# DevBoard.net
KiCad netlist of a schematic drawn in Altium Designer
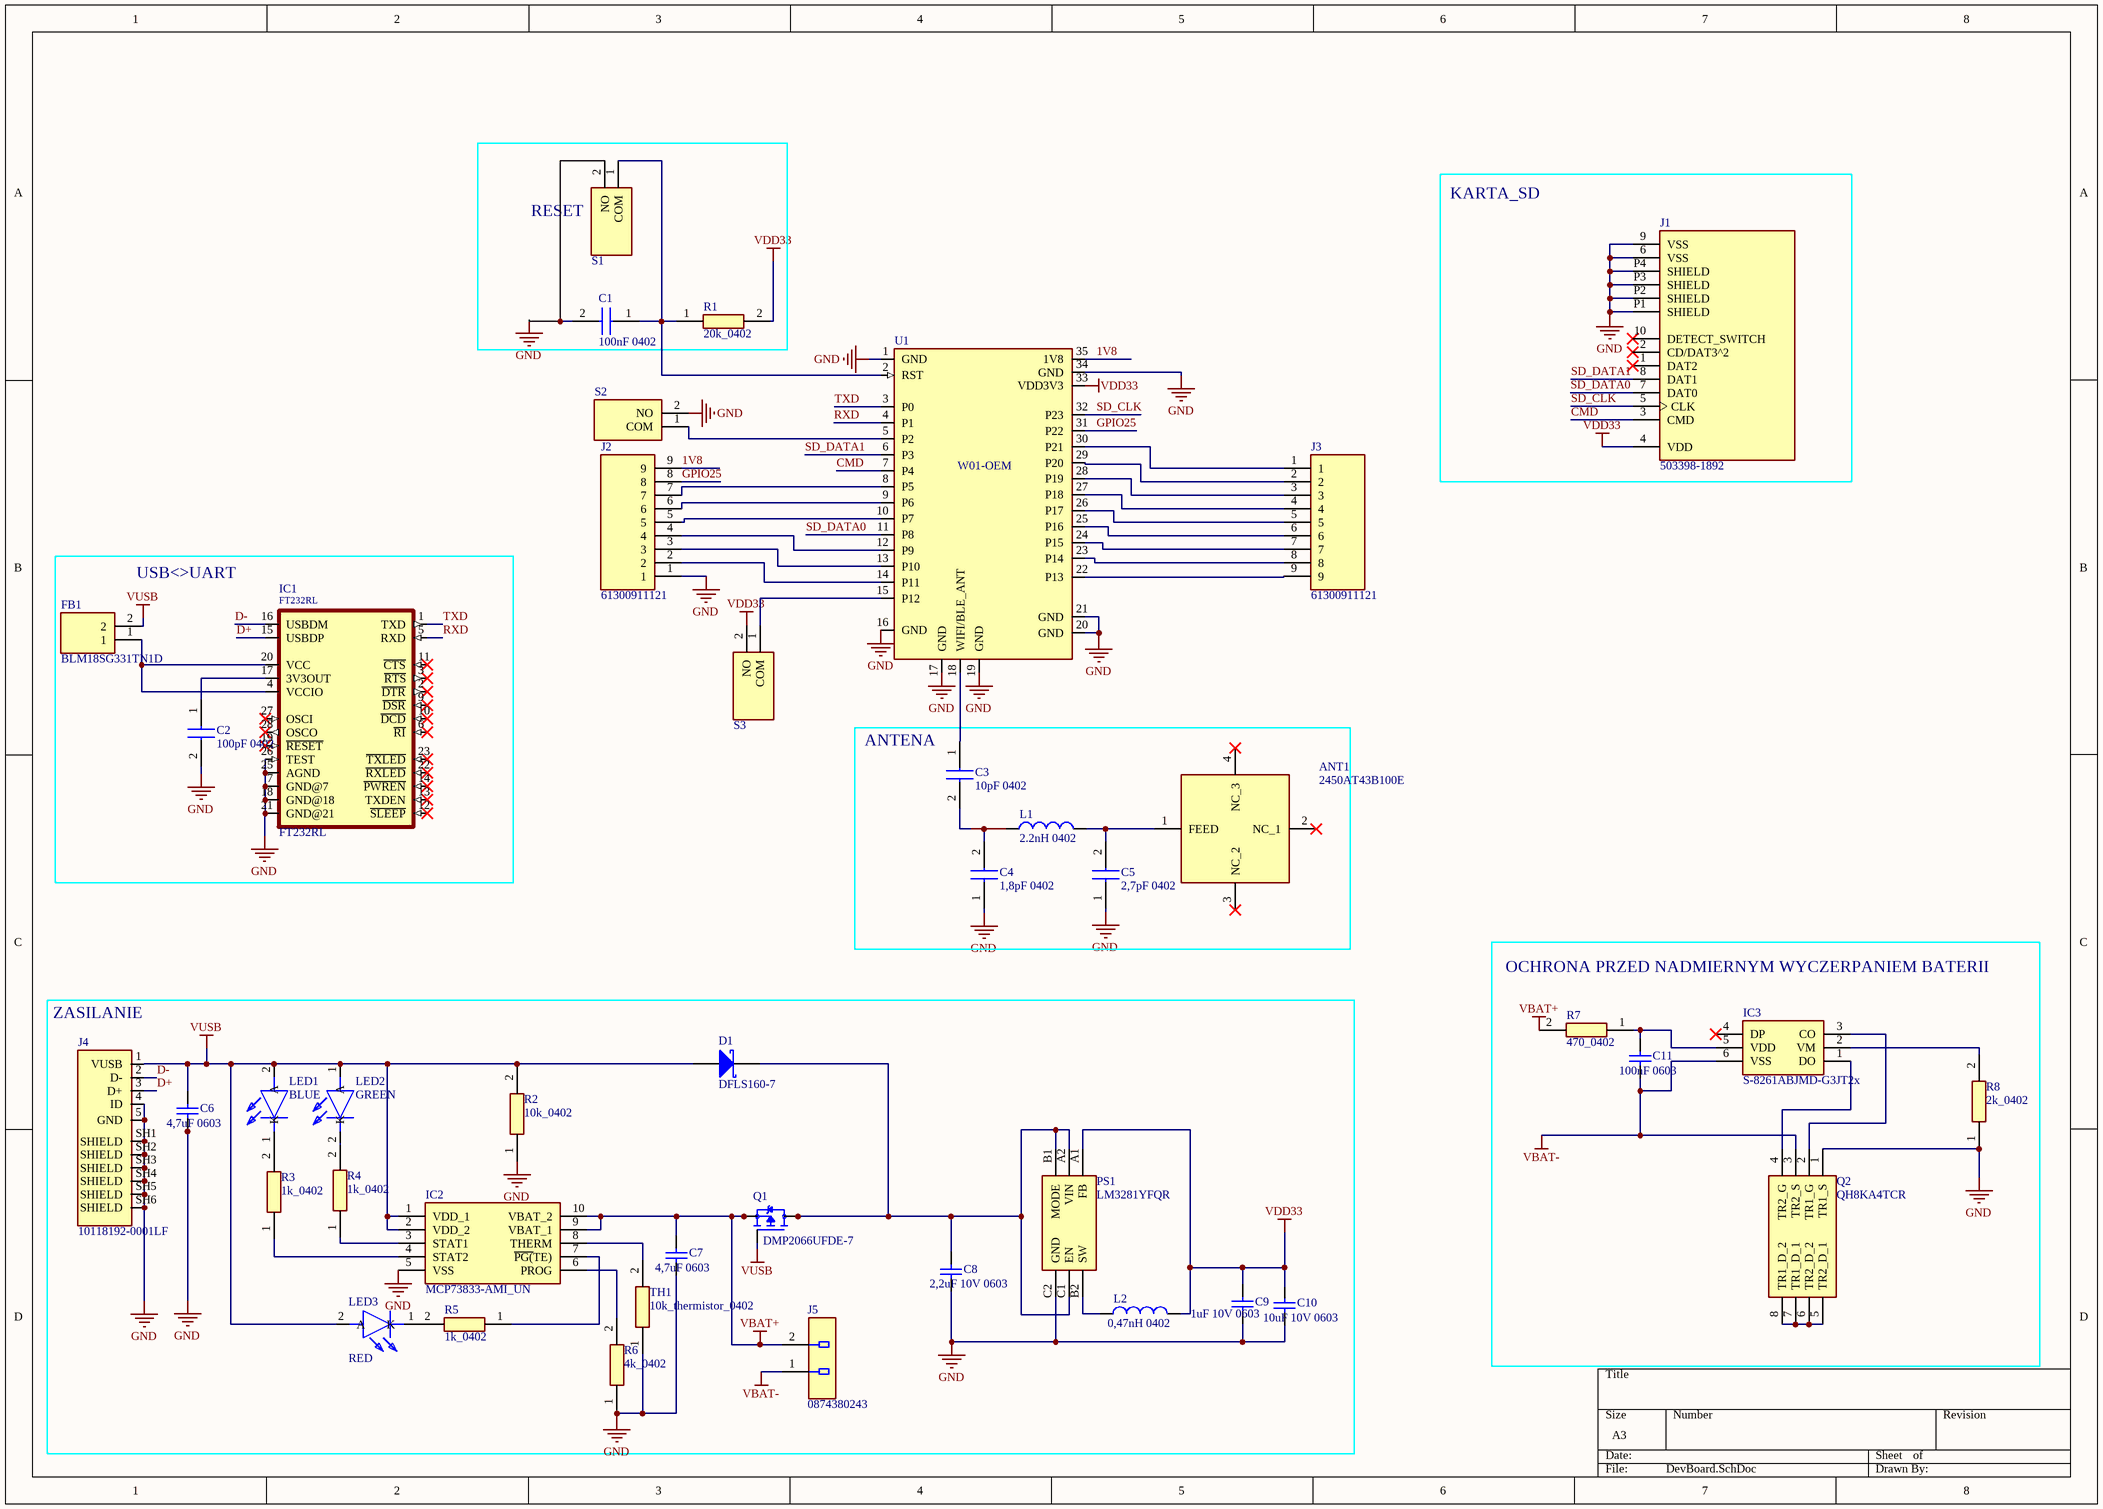
[diagram p0: DevBoard.SchDoc]

(export (version "E")
  (design (tool "Eeschema 10.0.6"))
  (components
    (comp (ref "ANT1")
      (value "2450AT43B100E")
      (footprint "SamacSys:2450AT43B100E")
      (description "Antenna")
      (fields (field (name "MOUSER PART NUMBER") "609-2450AT43B100E"))
      (libsource (lib "*") (part "2450AT43B100E"))
    )
    (comp (ref "C1")
      (value "100nF 0402")
      (footprint "SamacSys:CAPC1005X56N")
      (description "Capacitor")
      (fields
        (field (name "MANUFACTURER_PART_NUMBER") "04025A1R8BAT2A")
        (field (name "MOUSER PART NUMBER") "581-04025A1R8BAT2A")
      )
      (libsource (lib "*") (part "04025A1R8BAT2A"))
    )
    (comp (ref "C2")
      (value "100pF 0402")
      (footprint "SamacSys:CAPC1005X56N")
      (description "Capacitor")
      (fields
        (field (name "MANUFACTURER_PART_NUMBER") "04025A1R8BAT2A")
        (field (name "MOUSER PART NUMBER") "581-04025A1R8BAT2A")
      )
      (libsource (lib "*") (part "04025A1R8BAT2A"))
    )
    (comp (ref "C3")
      (value "10pF 0402")
      (footprint "SamacSys:CAPC1005X56N")
      (description "Capacitor")
      (fields
        (field (name "MANUFACTURER_PART_NUMBER") "04025A1R8BAT2A")
        (field (name "MOUSER PART NUMBER") "581-04025A1R8BAT2A")
      )
      (libsource (lib "*") (part "04025A1R8BAT2A"))
    )
    (comp (ref "C4")
      (value "1,8pF 0402")
      (footprint "SamacSys:CAPC1005X56N")
      (description "Capacitor")
      (fields
        (field (name "MANUFACTURER_PART_NUMBER") "04025A1R8BAT2A")
        (field (name "MOUSER PART NUMBER") "581-04025A1R8BAT2A")
      )
      (libsource (lib "*") (part "04025A1R8BAT2A"))
    )
    (comp (ref "C5")
      (value "2,7pF 0402")
      (footprint "SamacSys:CAPC1005X56N")
      (description "Capacitor")
      (fields
        (field (name "MANUFACTURER_PART_NUMBER") "04025A1R8BAT2A")
        (field (name "MOUSER PART NUMBER") "581-04025A1R8BAT2A")
      )
      (libsource (lib "*") (part "04025A1R8BAT2A"))
    )
    (comp (ref "C6")
      (value "4,7uF 0603")
      (footprint "CAPC0603(1608)100_L")
      (description "CAP 1uF 10V ±20% 0603 (1608 Metric) Thickness 1mm SMD")
      (fields (field (name "TOLERANCE") "Â±20%"))
      (libsource (lib "Altium Content Vault") (part "CMP-1035-02734-1"))
    )
    (comp (ref "C7")
      (value "4,7uF 0603")
      (footprint "CAPC0603(1608)100_L")
      (description "CAP 1uF 10V ±20% 0603 (1608 Metric) Thickness 1mm SMD")
      (fields (field (name "TOLERANCE") "Â±20%"))
      (libsource (lib "Altium Content Vault") (part "CMP-1035-02734-1"))
    )
    (comp (ref "C8")
      (value "2,2uF 10V 0603")
      (footprint "CAPC0603(1608)100_L")
      (description "CAP 1uF 10V ±20% 0603 (1608 Metric) Thickness 1mm SMD")
      (fields (field (name "TOLERANCE") "Â±20%"))
      (libsource (lib "Altium Content Vault") (part "CMP-1035-02734-1"))
    )
    (comp (ref "C9")
      (value "1uF 10V 0603")
      (footprint "CAPC0603(1608)100_L")
      (description "CAP 1uF 10V ±20% 0603 (1608 Metric) Thickness 1mm SMD")
      (fields (field (name "TOLERANCE") "Â±20%"))
      (libsource (lib "Altium Content Vault") (part "CAP"))
    )
    (comp (ref "C10")
      (value "10uF 10V 0603")
      (footprint "CAPC0603(1608)100_L")
      (description "CAP 1uF 10V ±20% 0603 (1608 Metric) Thickness 1mm SMD")
      (fields (field (name "TOLERANCE") "Â±20%"))
      (libsource (lib "Altium Content Vault") (part "CMP-1035-02734-1"))
    )
    (comp (ref "C11")
      (value "100nF 0603")
      (footprint "CAPC0603(1608)100_L")
      (description "CAP 1uF 10V ±20% 0603 (1608 Metric) Thickness 1mm SMD")
      (fields (field (name "TOLERANCE") "Â±20%"))
      (libsource (lib "Altium Content Vault") (part "CMP-1035-02734-1"))
    )
    (comp (ref "D1")
      (value "DFLS160-7")
      (footprint "DIOD-POWERDI123-2_V")
      (description "Schottky Barrier Rectifier, 60 V, 1 A, -65 to 150 degC, 2-Pin SMD, RoHS, Tape and Reel")
      (fields (field (name "MANUFACTURER") "Diodes Inc"))
      (libsource (lib "Altium Content Vault") (part "CMP-2000-07449-1"))
    )
    (comp (ref "FB1")
      (value "BLM18SG331TN1D")
      (footprint "SamacSys:BLM18SG121TN1J")
      (description "Ferrite Bead")
      (fields (field (name "MOUSER PART NUMBER") "81-BLM18SG331TN1D"))
      (libsource (lib "*") (part "BLM18SG331TN1D"))
    )
    (comp (ref "IC1")
      (value "FT232RL")
      (footprint "SSOP28-LD")
      (description "USB ë¸Œë¦¬ì§€, USB-UART USB 2.0 UART ì¸í„°íŽ˜ì´ìŠ¤ 28-SSOP")
      (fields (field (name "MF") "FTDI, Future"))
      (libsource (lib "FT232RL") (part "FT232RL"))
    )
    (comp (ref "IC2")
      (value "MCP73833-AMI_UN")
      (footprint "SamacSys:SOP50P490X110-10N")
      (description "Integrated Circuit")
      (fields
        (field (name "MANUFACTURER_PART_NUMBER") "MCP73833-AMI/UN")
        (field (name "MOUSER PART NUMBER") "579-MCP73833-AMI/UN")
      )
      (libsource (lib "*") (part "MCP73833-AMI_UN"))
    )
    (comp (ref "IC3")
      (value "S-8261ABJMD-G3JT2x")
      (footprint "SamacSys:SOT95P275X135-6N")
      (description "Integrated Circuit")
      (fields (field (name "MOUSER PART NUMBER") "628-S8261ACMMDG4MT2G"))
      (libsource (lib "*") (part "S-8261ACMMD-G4MT2U"))
    )
    (comp (ref "J1")
      (value "503398-1892")
      (footprint "MOLEX_503398-1892")
      (description "9 _8 + 1_ Position Card Connector microSDâ„¢ Surface Mount, Right Angle Gold")
      (fields (field (name "MP") "5033981892") (field (name "DIGI-KEY_PART_NUMBER") "WM11190CT-ND"))
      (libsource (lib "503398-1892") (part "503398-1892"))
    )
    (comp (ref "J2")
      (value "61300911121")
      (footprint "SamacSys:HDRV9W95P0X254_1X9_2286X254X874P")
      (description "Connector")
      (fields (field (name "MOUSER PART NUMBER") "710-61300911121"))
      (libsource (lib "") (part "61300911121_1"))
    )
    (comp (ref "J3")
      (value "61300911121")
      (footprint "SamacSys:HDRV9W95P0X254_1X9_2286X254X874P")
      (description "Connector")
      (fields (field (name "MOUSER PART NUMBER") "710-61300911121"))
      (libsource (lib "*") (part "61300911121"))
    )
    (comp (ref "J4")
      (value "10118192-0001LF")
      (footprint "SamacSys:101181920001LF")
      (description "USB - micro B USB 2.0 Receptacle Connector 5 Position Surface Mount, Right Angle")
      (fields (field (name "MF") "Amphenol ICC"))
      (libsource (lib "10118192-0001LF") (part "10118192-0001LF"))
    )
    (comp (ref "J5")
      (value "Conn_Molex_0874380243_eec")
      (footprint "Molex_0874380243_0")
      (description "CONN HEADER 2POS 1.5MM R/A SMD")
      (fields
        (field (name "PART NUMBER") "0874380243")
        (field (name "MANUFACTURER") "Molex")
        (field (name "MOUSER PART NUMBER") "538-87438-0243")
      )
      (libsource (lib "Conn_Molex_0874380243_eec") (part "Conn_Molex_0874380243_eec"))
    )
    (comp (ref "L1")
      (value "2.2nH 0402")
      (footprint "INDC1006X60X20LL10T10")
      (description "Chip Inductor, 10 nH, +/- 5%, 500 mA, -55 to 125 degC, 0402 (1005 Metric), RoHS, Tape and Reel")
      (fields (field (name "MANUFACTURER") "Murata"))
      (libsource (lib "Altium Content Vault") (part "IND-2"))
    )
    (comp (ref "L2")
      (value "0,47nH 0402")
      (footprint "INDC1006X60X20LL10T10")
      (description "Chip Inductor, 10 nH, +/- 5%, 500 mA, -55 to 125 degC, 0402 (1005 Metric), RoHS, Tape and Reel")
      (fields (field (name "MANUFACTURER") "Murata"))
      (libsource (lib "Altium Content Vault") (part "IND-2"))
    )
    (comp (ref "LED1")
      (value "BLUE")
      (footprint "SamacSys:KBDELPS212QHRI24Z55510S")
      (description "LED_BLUE")
      (fields
        (field (name "MANUFACTURER_PART_NUMBER") "KB DELPS2.12-QHRI-24-Z555-10-S")
        (field (name "MOUSER PART NUMBER") "720-KBDELPS212A6350")
      )
      (libsource (lib "*") (part "KB_DELPS2.12-QHRI-24-Z555-10-S"))
    )
    (comp (ref "LED2")
      (value "GREEN")
      (footprint "SamacSys:KGDELLS122JGKH24")
      (description "LED_GREEN")
      (fields
        (field (name "MANUFACTURER_PART_NUMBER") "KG DELLS1.22-JGKH-24")
        (field (name "MOUSER PART NUMBER") "720-KGDELLS122A4849")
      )
      (libsource (lib "*") (part "KG_DELLS1.22-JGKH-24"))
    )
    (comp (ref "LED3")
      (value "RED")
      (footprint "SamacSys:KRDELPS122UHVI26H3Q4")
      (description "LED_RED")
      (fields
        (field (name "MANUFACTURER_PART_NUMBER") "KR DELPS1.22-UHVI-26-H3Q4")
        (field (name "MOUSER PART NUMBER") "720-KRDELPS122A5163")
      )
      (libsource (lib "*") (part "KR_DELPS1.22-UHVI-26-H3Q4"))
    )
    (comp (ref "PS1")
      (value "LM3281YFQR")
      (footprint "SamacSys:BGA6C40P2X3_116X144X68")
      (description "Power Supply")
      (fields (field (name "MOUSER PART NUMBER") "595-LM3281YFQR"))
      (libsource (lib "*") (part "LM3281YFQR"))
    )
    (comp (ref "Q1")
      (value "DMP2066UFDE-7")
      (footprint "MOSFET_DMP2066UFDE-7")
      (description "P-Channel 20V 6.2A (Ta) 660mW (Ta) Surface Mount U-DFN2020-6 (Type E)")
      (fields (field (name "MF") "Diodes Inc."))
      (libsource (lib "DMP2066UFDE-7") (part "DMP2066UFDE-7"))
    )
    (comp (ref "Q2")
      (value "QH8KA4TCR")
      (footprint "SamacSys:SOTFL65P280X85-8N")
      (description "MOSFET (N-Channel)")
      (fields (field (name "MOUSER PART NUMBER") "755-QH8KA4TCR"))
      (libsource (lib "*") (part "QH8KA4TCR"))
    )
    (comp (ref "R1")
      (value "20k_0402")
      (footprint "SamacSys:RESC1005X40N")
      (description "Resistor")
      (fields
        (field (name "MANUFACTURER_PART_NUMBER") "CR0402-FX-2002GLF")
        (field (name "MOUSER PART NUMBER") "652-CR0402FX-2002GLF")
      )
      (libsource (lib "") (part "CR0402-FX-2002GLF_2"))
    )
    (comp (ref "R2")
      (value "10k_0402")
      (footprint "SamacSys:RESC1005X40N")
      (description "Resistor")
      (fields
        (field (name "MANUFACTURER_PART_NUMBER") "CR0402-FX-2002GLF")
        (field (name "MOUSER PART NUMBER") "652-CR0402FX-2002GLF")
      )
      (libsource (lib "*") (part "CR0402-FX-2002GLF"))
    )
    (comp (ref "R3")
      (value "1k_0402")
      (footprint "SamacSys:RESC1005X40N")
      (description "Resistor")
      (fields
        (field (name "MANUFACTURER_PART_NUMBER") "CR0402-FX-2002GLF")
        (field (name "MOUSER PART NUMBER") "652-CR0402FX-2002GLF")
      )
      (libsource (lib "*") (part "CR0402-FX-2002GLF"))
    )
    (comp (ref "R4")
      (value "1k_0402")
      (footprint "SamacSys:RESC1005X40N")
      (description "Resistor")
      (fields
        (field (name "MANUFACTURER_PART_NUMBER") "CR0402-FX-2002GLF")
        (field (name "MOUSER PART NUMBER") "652-CR0402FX-2002GLF")
      )
      (libsource (lib "*") (part "CR0402-FX-2002GLF"))
    )
    (comp (ref "R5")
      (value "1k_0402")
      (footprint "SamacSys:RESC1005X40N")
      (description "Resistor")
      (fields
        (field (name "MANUFACTURER_PART_NUMBER") "CR0402-FX-2002GLF")
        (field (name "MOUSER PART NUMBER") "652-CR0402FX-2002GLF")
      )
      (libsource (lib "") (part "CR0402-FX-2002GLF_1"))
    )
    (comp (ref "R6")
      (value "4k_0402")
      (footprint "SamacSys:RESC1005X40N")
      (description "Resistor")
      (fields
        (field (name "MANUFACTURER_PART_NUMBER") "CR0402-FX-2002GLF")
        (field (name "MOUSER PART NUMBER") "652-CR0402FX-2002GLF")
      )
      (libsource (lib "*") (part "CR0402-FX-2002GLF"))
    )
    (comp (ref "R7")
      (value "470_0402")
      (footprint "SamacSys:RESC1005X40N")
      (description "Resistor")
      (fields
        (field (name "MANUFACTURER_PART_NUMBER") "CR0402-FX-2002GLF")
        (field (name "MOUSER PART NUMBER") "652-CR0402FX-2002GLF")
      )
      (libsource (lib "") (part "CR0402-FX-2002GLF_1"))
    )
    (comp (ref "R8")
      (value "2k_0402")
      (footprint "SamacSys:RESC1005X40N")
      (description "Resistor")
      (fields
        (field (name "MANUFACTURER_PART_NUMBER") "CR0402-FX-2002GLF")
        (field (name "MOUSER PART NUMBER") "652-CR0402FX-2002GLF")
      )
      (libsource (lib "*") (part "CR0402-FX-2002GLF"))
    )
    (comp (ref "S1")
      (value "PTS636_SM43J_SMTR_LFS")
      (footprint "SamacSys:PTS636SM43JSMTRLFS")
      (description "Switch")
      (fields
        (field (name "MANUFACTURER_PART_NUMBER") "PTS636 SM43J SMTR LFS")
        (field (name "MOUSER PART NUMBER") "611-PTS636SM43JSMTRL")
      )
      (libsource (lib "") (part "PTS636_SM43J_SMTR_LFS_1"))
    )
    (comp (ref "S2")
      (value "PTS636_SM43J_SMTR_LFS")
      (footprint "SamacSys:PTS636SM43JSMTRLFS")
      (description "Switch")
      (fields
        (field (name "MANUFACTURER_PART_NUMBER") "PTS636 SM43J SMTR LFS")
        (field (name "MOUSER PART NUMBER") "611-PTS636SM43JSMTRL")
      )
      (libsource (lib "*") (part "PTS636_SM43J_SMTR_LFS"))
    )
    (comp (ref "S3")
      (value "PTS636_SM43J_SMTR_LFS")
      (footprint "SamacSys:PTS636SM43JSMTRLFS")
      (description "Switch")
      (fields
        (field (name "MANUFACTURER_PART_NUMBER") "PTS636 SM43J SMTR LFS")
        (field (name "MOUSER PART NUMBER") "611-PTS636SM43JSMTRL")
      )
      (libsource (lib "") (part "PTS636_SM43J_SMTR_LFS_1"))
    )
    (comp (ref "TH1")
      (value "10k_thermistor_0402")
      (footprint "SamacSys:RESC1005X40N")
      (description "NCU15XH103D60RC")
      (fields
        (field (name "MANUFACTURER_PART_NUMBER") "CR0402-FX-2002GLF")
        (field (name "MOUSER PART NUMBER") "652-CR0402FX-2002GLF")
      )
      (libsource (lib "*") (part "CR0402-FX-2002GLF"))
    )
    (comp (ref "U1")
      (value "W01-OEM")
      (footprint "SnapEDApcb:PYCOM_W01-OEM")
      (fields (field (name "MF") "Pycom"))
      (libsource (lib "SnapEDAsch") (part "W01-OEM"))
    )
  )
  (nets
    (net (code "1") (name "/1V8") (class "Default")
      (node (ref "J2") (pin "9") (pinfunction "9_9") (pintype "passive"))
      (node (ref "U1") (pin "35") (pinfunction "1V8_35") (pintype "power_in"))
    )
    (net (code "2") (name "/CMD") (class "Default")
      (node (ref "J1") (pin "3") (pinfunction "CMD_3") (pintype "passive"))
      (node (ref "U1") (pin "7") (pinfunction "P4_7") (pintype "bidirectional"))
    )
    (net (code "3") (name "/D+") (class "Default")
      (node (ref "IC1") (pin "15") (pinfunction "USBDP_15") (pintype "bidirectional"))
      (node (ref "J4") (pin "3") (pinfunction "D+_3") (pintype "passive"))
    )
    (net (code "4") (name "/D-") (class "Default")
      (node (ref "IC1") (pin "16") (pinfunction "USBDM_16") (pintype "bidirectional"))
      (node (ref "J4") (pin "2") (pinfunction "D-_2") (pintype "passive"))
    )
    (net (code "5") (name "/GPIO25") (class "Default")
      (node (ref "J2") (pin "8") (pinfunction "8_8") (pintype "passive"))
      (node (ref "U1") (pin "31") (pinfunction "P22_31") (pintype "bidirectional"))
    )
    (net (code "6") (name "/RXD") (class "Default")
      (node (ref "IC1") (pin "5") (pinfunction "RXD_5") (pintype "input"))
      (node (ref "U1") (pin "4") (pinfunction "P1_4") (pintype "bidirectional"))
    )
    (net (code "7") (name "/SD_CLK") (class "Default")
      (node (ref "J1") (pin "5") (pinfunction "CLK_5") (pintype "passive"))
      (node (ref "U1") (pin "32") (pinfunction "P23_32") (pintype "bidirectional"))
    )
    (net (code "8") (name "/SD_DATA0") (class "Default")
      (node (ref "J1") (pin "7") (pinfunction "DAT0_7") (pintype "passive"))
      (node (ref "U1") (pin "11") (pinfunction "P8_11") (pintype "bidirectional"))
    )
    (net (code "9") (name "/SD_DATA1") (class "Default")
      (node (ref "J1") (pin "8") (pinfunction "DAT1_8") (pintype "passive"))
      (node (ref "U1") (pin "6") (pinfunction "P3_6") (pintype "bidirectional"))
    )
    (net (code "10") (name "/TXD") (class "Default")
      (node (ref "IC1") (pin "1") (pinfunction "TXD_1") (pintype "output"))
      (node (ref "U1") (pin "3") (pinfunction "P0_3") (pintype "bidirectional"))
    )
    (net (code "11") (name "GND") (class "Default")
      (node (ref "C1") (pin "2") (pinfunction "2_2") (pintype "passive"))
      (node (ref "C10") (pin "1") (pinfunction "1_1") (pintype "passive"))
      (node (ref "C2") (pin "2") (pinfunction "2_2") (pintype "passive"))
      (node (ref "C4") (pin "1") (pinfunction "1_1") (pintype "passive"))
      (node (ref "C5") (pin "1") (pinfunction "1_1") (pintype "passive"))
      (node (ref "C6") (pin "1") (pinfunction "1_1") (pintype "passive"))
      (node (ref "C7") (pin "1") (pinfunction "1_1") (pintype "passive"))
      (node (ref "C8") (pin "1") (pinfunction "1_1") (pintype "passive"))
      (node (ref "C9") (pin "1") (pinfunction "1_1") (pintype "passive"))
      (node (ref "IC1") (pin "18") (pinfunction "GND@18_18") (pintype "power_in"))
      (node (ref "IC1") (pin "21") (pinfunction "GND@21_21") (pintype "power_in"))
      (node (ref "IC1") (pin "25") (pinfunction "AGND_25") (pintype "power_in"))
      (node (ref "IC1") (pin "26") (pinfunction "TEST_26") (pintype "input"))
      (node (ref "IC1") (pin "7") (pinfunction "GND@7_7") (pintype "power_in"))
      (node (ref "IC2") (pin "5") (pinfunction "VSS_5") (pintype "passive"))
      (node (ref "J1") (pin "6") (pinfunction "VSS_6") (pintype "power_in"))
      (node (ref "J1") (pin "9") (pinfunction "VSS_9") (pintype "power_in"))
      (node (ref "J1") (pin "P1") (pinfunction "SHIELD_P1") (pintype "passive"))
      (node (ref "J1") (pin "P2") (pinfunction "SHIELD_P2") (pintype "passive"))
      (node (ref "J1") (pin "P3") (pinfunction "SHIELD_P3") (pintype "passive"))
      (node (ref "J1") (pin "P4") (pinfunction "SHIELD_P4") (pintype "passive"))
      (node (ref "J2") (pin "1") (pinfunction "1_1") (pintype "passive"))
      (node (ref "J4") (pin "4") (pinfunction "ID_4") (pintype "passive"))
      (node (ref "J4") (pin "5") (pinfunction "GND_5") (pintype "passive"))
      (node (ref "J4") (pin "SH1") (pinfunction "SHIELD_SH1") (pintype "passive"))
      (node (ref "J4") (pin "SH2") (pinfunction "SHIELD_SH2") (pintype "passive"))
      (node (ref "J4") (pin "SH3") (pinfunction "SHIELD_SH3") (pintype "passive"))
      (node (ref "J4") (pin "SH4") (pinfunction "SHIELD_SH4") (pintype "passive"))
      (node (ref "J4") (pin "SH5") (pinfunction "SHIELD_SH5") (pintype "passive"))
      (node (ref "J4") (pin "SH6") (pinfunction "SHIELD_SH6") (pintype "passive"))
      (node (ref "PS1") (pin "C2") (pinfunction "GND_C2") (pintype "passive"))
      (node (ref "Q2") (pin "1") (pinfunction "TR1_S_1") (pintype "passive"))
      (node (ref "R2") (pin "1") (pinfunction "1_1") (pintype "passive"))
      (node (ref "R6") (pin "1") (pinfunction "1_1") (pintype "passive"))
      (node (ref "R8") (pin "1") (pinfunction "1_1") (pintype "passive"))
      (node (ref "S1") (pin "2") (pinfunction "NO_2") (pintype "passive"))
      (node (ref "S2") (pin "2") (pinfunction "NO_2") (pintype "passive"))
      (node (ref "TH1") (pin "1") (pinfunction "1_1") (pintype "passive"))
      (node (ref "U1") (pin "1") (pinfunction "GND_1") (pintype "power_in"))
      (node (ref "U1") (pin "16") (pinfunction "GND_16") (pintype "power_in"))
      (node (ref "U1") (pin "17") (pinfunction "GND_17") (pintype "power_in"))
      (node (ref "U1") (pin "19") (pinfunction "GND_19") (pintype "power_in"))
      (node (ref "U1") (pin "20") (pinfunction "GND_20") (pintype "power_in"))
      (node (ref "U1") (pin "21") (pinfunction "GND_21") (pintype "power_in"))
      (node (ref "U1") (pin "34") (pinfunction "GND_34") (pintype "power_in"))
    )
    (net (code "12") (name "Net-(ANT1-FEED)") (class "Default")
      (node (ref "ANT1") (pin "1") (pinfunction "FEED_1") (pintype "passive"))
      (node (ref "C5") (pin "2") (pinfunction "2_2") (pintype "passive"))
      (node (ref "L1") (pin "2") (pinfunction "2_2") (pintype "passive"))
    )
    (net (code "13") (name "Net-(C3-Pad2)") (class "Default")
      (node (ref "C3") (pin "2") (pinfunction "2_2") (pintype "passive"))
      (node (ref "C4") (pin "2") (pinfunction "2_2") (pintype "passive"))
      (node (ref "L1") (pin "1") (pinfunction "1_1") (pintype "passive"))
    )
    (net (code "14") (name "Net-(D1-K)") (class "Default")
      (node (ref "C8") (pin "2") (pinfunction "2_2") (pintype "passive"))
      (node (ref "D1") (pin "2") (pinfunction "K_2") (pintype "passive"))
      (node (ref "PS1") (pin "A2") (pinfunction "VIN_A2") (pintype "passive"))
      (node (ref "PS1") (pin "B1") (pinfunction "MODE_B1") (pintype "passive"))
      (node (ref "PS1") (pin "C1") (pinfunction "EN_C1") (pintype "passive"))
      (node (ref "Q1") (pin "1") (pinfunction "D_1") (pintype "passive"))
      (node (ref "Q1") (pin "2") (pinfunction "D_2") (pintype "passive"))
      (node (ref "Q1") (pin "5") (pinfunction "D_5") (pintype "passive"))
      (node (ref "Q1") (pin "6") (pinfunction "D_6") (pintype "passive"))
    )
    (net (code "15") (name "Net-(IC1-3V3OUT)") (class "Default")
      (node (ref "C2") (pin "1") (pinfunction "1_1") (pintype "passive"))
      (node (ref "IC1") (pin "17") (pinfunction "3V3OUT_17") (pintype "power_in"))
    )
    (net (code "16") (name "Net-(IC1-VCC)") (class "Default")
      (node (ref "FB1") (pin "1") (pinfunction "1_1") (pintype "passive"))
      (node (ref "IC1") (pin "20") (pinfunction "VCC_20") (pintype "power_in"))
      (node (ref "IC1") (pin "4") (pinfunction "VCCIO_4") (pintype "power_in"))
    )
    (net (code "17") (name "Net-(IC2-PROG)") (class "Default")
      (node (ref "IC2") (pin "6") (pinfunction "PROG_6") (pintype "passive"))
      (node (ref "R6") (pin "2") (pinfunction "2_2") (pintype "passive"))
    )
    (net (code "18") (name "Net-(IC2-STAT1)") (class "Default")
      (node (ref "IC2") (pin "3") (pinfunction "STAT1_3") (pintype "passive"))
      (node (ref "R4") (pin "1") (pinfunction "1_1") (pintype "passive"))
    )
    (net (code "19") (name "Net-(IC2-STAT2)") (class "Default")
      (node (ref "IC2") (pin "4") (pinfunction "STAT2_4") (pintype "passive"))
      (node (ref "R3") (pin "1") (pinfunction "1_1") (pintype "passive"))
    )
    (net (code "20") (name "Net-(IC2-THERM)") (class "Default")
      (node (ref "IC2") (pin "8") (pinfunction "THERM_8") (pintype "passive"))
      (node (ref "TH1") (pin "2") (pinfunction "2_2") (pintype "passive"))
    )
    (net (code "21") (name "Net-(IC2-~{PG(}TE))") (class "Default")
      (node (ref "IC2") (pin "7") (pinfunction "~{PG(}TE)_7") (pintype "passive"))
      (node (ref "R5") (pin "1") (pinfunction "1_1") (pintype "passive"))
    )
    (net (code "22") (name "Net-(IC3-CO)") (class "Default")
      (node (ref "IC3") (pin "3") (pinfunction "CO_3") (pintype "passive"))
      (node (ref "Q2") (pin "2") (pinfunction "TR1_G_2") (pintype "passive"))
    )
    (net (code "23") (name "Net-(IC3-DO)") (class "Default")
      (node (ref "IC3") (pin "1") (pinfunction "DO_1") (pintype "passive"))
      (node (ref "Q2") (pin "4") (pinfunction "TR2_G_4") (pintype "passive"))
    )
    (net (code "24") (name "Net-(IC3-VDD)") (class "Default")
      (node (ref "C11") (pin "2") (pinfunction "2_2") (pintype "passive"))
      (node (ref "IC3") (pin "5") (pinfunction "VDD_5") (pintype "passive"))
      (node (ref "R7") (pin "1") (pinfunction "1_1") (pintype "passive"))
    )
    (net (code "25") (name "Net-(IC3-VM)") (class "Default")
      (node (ref "IC3") (pin "2") (pinfunction "VM_2") (pintype "passive"))
      (node (ref "R8") (pin "2") (pinfunction "2_2") (pintype "passive"))
    )
    (net (code "26") (name "Net-(LED1-K)") (class "Default")
      (node (ref "LED1") (pin "1") (pinfunction "K_1") (pintype "passive"))
      (node (ref "R3") (pin "2") (pinfunction "2_2") (pintype "passive"))
    )
    (net (code "27") (name "Net-(LED2-K)") (class "Default")
      (node (ref "LED2") (pin "2") (pinfunction "K_2") (pintype "passive"))
      (node (ref "R4") (pin "2") (pinfunction "2_2") (pintype "passive"))
    )
    (net (code "28") (name "Net-(LED3-K)") (class "Default")
      (node (ref "LED3") (pin "1") (pinfunction "K_1") (pintype "passive"))
      (node (ref "R5") (pin "2") (pinfunction "2_2") (pintype "passive"))
    )
    (net (code "29") (name "Net-(PS1-SW)") (class "Default")
      (node (ref "L2") (pin "1") (pinfunction "1_1") (pintype "passive"))
      (node (ref "PS1") (pin "B2") (pinfunction "SW_B2") (pintype "passive"))
    )
    (net (code "30") (name "Net-(Q2-TR1_D_1)") (class "Default")
      (node (ref "Q2") (pin "5") (pinfunction "TR2_D_1_5") (pintype "passive"))
      (node (ref "Q2") (pin "6") (pinfunction "TR2_D_2_6") (pintype "passive"))
      (node (ref "Q2") (pin "7") (pinfunction "TR1_D_1_7") (pintype "passive"))
      (node (ref "Q2") (pin "8") (pinfunction "TR1_D_2_8") (pintype "passive"))
    )
    (net (code "31") (name "Net-(S1-COM)") (class "Default")
      (node (ref "C1") (pin "1") (pinfunction "1_1") (pintype "passive"))
      (node (ref "R1") (pin "1") (pinfunction "1_1") (pintype "passive"))
      (node (ref "S1") (pin "1") (pinfunction "COM_1") (pintype "passive"))
      (node (ref "U1") (pin "2") (pinfunction "RST_2") (pintype "input"))
    )
    (net (code "32") (name "Net-(S2-COM)") (class "Default")
      (node (ref "S2") (pin "1") (pinfunction "COM_1") (pintype "passive"))
      (node (ref "U1") (pin "5") (pinfunction "P2_5") (pintype "bidirectional"))
    )
    (net (code "33") (name "Net-(S3-COM)") (class "Default")
      (node (ref "S3") (pin "1") (pinfunction "COM_1") (pintype "passive"))
      (node (ref "U1") (pin "15") (pinfunction "P12_15") (pintype "bidirectional"))
    )
    (net (code "34") (name "Net-(U1-P5)") (class "Default")
      (node (ref "J2") (pin "7") (pinfunction "7_7") (pintype "passive"))
      (node (ref "U1") (pin "8") (pinfunction "P5_8") (pintype "bidirectional"))
    )
    (net (code "35") (name "Net-(U1-P6)") (class "Default")
      (node (ref "J2") (pin "6") (pinfunction "6_6") (pintype "passive"))
      (node (ref "U1") (pin "9") (pinfunction "P6_9") (pintype "bidirectional"))
    )
    (net (code "36") (name "Net-(U1-P7)") (class "Default")
      (node (ref "J2") (pin "5") (pinfunction "5_5") (pintype "passive"))
      (node (ref "U1") (pin "10") (pinfunction "P7_10") (pintype "bidirectional"))
    )
    (net (code "37") (name "Net-(U1-P9)") (class "Default")
      (node (ref "J2") (pin "4") (pinfunction "4_4") (pintype "passive"))
      (node (ref "U1") (pin "12") (pinfunction "P9_12") (pintype "bidirectional"))
    )
    (net (code "38") (name "Net-(U1-P10)") (class "Default")
      (node (ref "J2") (pin "3") (pinfunction "3_3") (pintype "passive"))
      (node (ref "U1") (pin "13") (pinfunction "P10_13") (pintype "bidirectional"))
    )
    (net (code "39") (name "Net-(U1-P11)") (class "Default")
      (node (ref "J2") (pin "2") (pinfunction "2_2") (pintype "passive"))
      (node (ref "U1") (pin "14") (pinfunction "P11_14") (pintype "bidirectional"))
    )
    (net (code "40") (name "Net-(U1-P13)") (class "Default")
      (node (ref "J3") (pin "9") (pinfunction "9_9") (pintype "passive"))
      (node (ref "U1") (pin "22") (pinfunction "P13_22") (pintype "bidirectional"))
    )
    (net (code "41") (name "Net-(U1-P14)") (class "Default")
      (node (ref "J3") (pin "8") (pinfunction "8_8") (pintype "passive"))
      (node (ref "U1") (pin "23") (pinfunction "P14_23") (pintype "bidirectional"))
    )
    (net (code "42") (name "Net-(U1-P15)") (class "Default")
      (node (ref "J3") (pin "7") (pinfunction "7_7") (pintype "passive"))
      (node (ref "U1") (pin "24") (pinfunction "P15_24") (pintype "bidirectional"))
    )
    (net (code "43") (name "Net-(U1-P16)") (class "Default")
      (node (ref "J3") (pin "6") (pinfunction "6_6") (pintype "passive"))
      (node (ref "U1") (pin "25") (pinfunction "P16_25") (pintype "bidirectional"))
    )
    (net (code "44") (name "Net-(U1-P17)") (class "Default")
      (node (ref "J3") (pin "5") (pinfunction "5_5") (pintype "passive"))
      (node (ref "U1") (pin "26") (pinfunction "P17_26") (pintype "bidirectional"))
    )
    (net (code "45") (name "Net-(U1-P18)") (class "Default")
      (node (ref "J3") (pin "4") (pinfunction "4_4") (pintype "passive"))
      (node (ref "U1") (pin "27") (pinfunction "P18_27") (pintype "bidirectional"))
    )
    (net (code "46") (name "Net-(U1-P19)") (class "Default")
      (node (ref "J3") (pin "3") (pinfunction "3_3") (pintype "passive"))
      (node (ref "U1") (pin "28") (pinfunction "P19_28") (pintype "bidirectional"))
    )
    (net (code "47") (name "Net-(U1-P20)") (class "Default")
      (node (ref "J3") (pin "2") (pinfunction "2_2") (pintype "passive"))
      (node (ref "U1") (pin "29") (pinfunction "P20_29") (pintype "bidirectional"))
    )
    (net (code "48") (name "Net-(U1-P21)") (class "Default")
      (node (ref "J3") (pin "1") (pinfunction "1_1") (pintype "passive"))
      (node (ref "U1") (pin "30") (pinfunction "P21_30") (pintype "bidirectional"))
    )
    (net (code "49") (name "Net-(U1-WIFI{slash}BLE_ANT)") (class "Default")
      (node (ref "C3") (pin "1") (pinfunction "1_1") (pintype "passive"))
      (node (ref "U1") (pin "18") (pinfunction "WIFI/BLE_ANT_18") (pintype "bidirectional"))
    )
    (net (code "50") (name "VBAT+") (class "Default")
      (node (ref "C7") (pin "2") (pinfunction "2_2") (pintype "passive"))
      (node (ref "IC2") (pin "10") (pinfunction "VBAT_2_10") (pintype "passive"))
      (node (ref "IC2") (pin "9") (pinfunction "VBAT_1_9") (pintype "passive"))
      (node (ref "J5") (pin "2") (pinfunction "2_2") (pintype "passive"))
      (node (ref "Q1") (pin "4") (pinfunction "S_4") (pintype "passive"))
      (node (ref "Q1") (pin "7") (pinfunction "S_7") (pintype "passive"))
      (node (ref "R7") (pin "2") (pinfunction "2_2") (pintype "passive"))
    )
    (net (code "51") (name "VBAT-") (class "Default")
      (node (ref "C11") (pin "1") (pinfunction "1_1") (pintype "passive"))
      (node (ref "IC3") (pin "6") (pinfunction "VSS_6") (pintype "passive"))
      (node (ref "J5") (pin "1") (pinfunction "1_1") (pintype "passive"))
      (node (ref "Q2") (pin "3") (pinfunction "TR2_S_3") (pintype "passive"))
    )
    (net (code "52") (name "VDD33") (class "Default")
      (node (ref "C10") (pin "2") (pinfunction "2_2") (pintype "passive"))
      (node (ref "C9") (pin "2") (pinfunction "2_2") (pintype "passive"))
      (node (ref "J1") (pin "4") (pinfunction "VDD_4") (pintype "power_in"))
      (node (ref "L2") (pin "2") (pinfunction "2_2") (pintype "passive"))
      (node (ref "PS1") (pin "A1") (pinfunction "FB_A1") (pintype "passive"))
      (node (ref "R1") (pin "2") (pinfunction "2_2") (pintype "passive"))
      (node (ref "S3") (pin "2") (pinfunction "NO_2") (pintype "passive"))
      (node (ref "U1") (pin "33") (pinfunction "VDD3V3_33") (pintype "power_in"))
    )
    (net (code "53") (name "VUSB") (class "Default")
      (node (ref "C6") (pin "2") (pinfunction "2_2") (pintype "passive"))
      (node (ref "D1") (pin "1") (pinfunction "A_1") (pintype "passive"))
      (node (ref "FB1") (pin "2") (pinfunction "2_2") (pintype "passive"))
      (node (ref "IC2") (pin "1") (pinfunction "VDD_1_1") (pintype "passive"))
      (node (ref "IC2") (pin "2") (pinfunction "VDD_2_2") (pintype "passive"))
      (node (ref "J4") (pin "1") (pinfunction "VUSB_1") (pintype "passive"))
      (node (ref "LED1") (pin "2") (pinfunction "A_2") (pintype "passive"))
      (node (ref "LED2") (pin "1") (pinfunction "A_1") (pintype "passive"))
      (node (ref "LED3") (pin "2") (pinfunction "A_2") (pintype "passive"))
      (node (ref "Q1") (pin "3") (pinfunction "G_3") (pintype "passive"))
      (node (ref "R2") (pin "2") (pinfunction "2_2") (pintype "passive"))
    )
    (net (code "54") (name "unconnected-(ANT1-NC_1-Pad2)") (class "Default")
      (node (ref "ANT1") (pin "2") (pinfunction "NC_1_2") (pintype "passive+no_connect"))
    )
    (net (code "55") (name "unconnected-(ANT1-NC_2-Pad3)") (class "Default")
      (node (ref "ANT1") (pin "3") (pinfunction "NC_2_3") (pintype "passive+no_connect"))
    )
    (net (code "56") (name "unconnected-(ANT1-NC_3-Pad4)") (class "Default")
      (node (ref "ANT1") (pin "4") (pinfunction "NC_3_4") (pintype "passive+no_connect"))
    )
    (net (code "57") (name "unconnected-(IC1-OSCI-Pad27)") (class "Default")
      (node (ref "IC1") (pin "27") (pinfunction "OSCI_27") (pintype "input+no_connect"))
    )
    (net (code "58") (name "unconnected-(IC1-OSCO-Pad28)") (class "Default")
      (node (ref "IC1") (pin "28") (pinfunction "OSCO_28") (pintype "output+no_connect"))
    )
    (net (code "59") (name "unconnected-(IC1-TXDEN-Pad13)") (class "Default")
      (node (ref "IC1") (pin "13") (pinfunction "TXDEN_13") (pintype "input+no_connect"))
    )
    (net (code "60") (name "unconnected-(IC1-~{CTS}-Pad11)") (class "Default")
      (node (ref "IC1") (pin "11") (pinfunction "~{CTS}_11") (pintype "input+no_connect"))
    )
    (net (code "61") (name "unconnected-(IC1-~{DCD}-Pad10)") (class "Default")
      (node (ref "IC1") (pin "10") (pinfunction "~{DCD}_10") (pintype "input+no_connect"))
    )
    (net (code "62") (name "unconnected-(IC1-~{DSR}-Pad9)") (class "Default")
      (node (ref "IC1") (pin "9") (pinfunction "~{DSR}_9") (pintype "input+no_connect"))
    )
    (net (code "63") (name "unconnected-(IC1-~{DTR}-Pad2)") (class "Default")
      (node (ref "IC1") (pin "2") (pinfunction "~{DTR}_2") (pintype "output+no_connect"))
    )
    (net (code "64") (name "unconnected-(IC1-~{PWREN}-Pad14)") (class "Default")
      (node (ref "IC1") (pin "14") (pinfunction "~{PWREN}_14") (pintype "input+no_connect"))
    )
    (net (code "65") (name "unconnected-(IC1-~{RESET}-Pad19)") (class "Default")
      (node (ref "IC1") (pin "19") (pinfunction "~{RESET}_19") (pintype "input+no_connect"))
    )
    (net (code "66") (name "unconnected-(IC1-~{RI}-Pad6)") (class "Default")
      (node (ref "IC1") (pin "6") (pinfunction "~{RI}_6") (pintype "input+no_connect"))
    )
    (net (code "67") (name "unconnected-(IC1-~{RTS}-Pad3)") (class "Default")
      (node (ref "IC1") (pin "3") (pinfunction "~{RTS}_3") (pintype "output+no_connect"))
    )
    (net (code "68") (name "unconnected-(IC1-~{RXLED}-Pad22)") (class "Default")
      (node (ref "IC1") (pin "22") (pinfunction "~{RXLED}_22") (pintype "input+no_connect"))
    )
    (net (code "69") (name "unconnected-(IC1-~{SLEEP}-Pad12)") (class "Default")
      (node (ref "IC1") (pin "12") (pinfunction "~{SLEEP}_12") (pintype "input+no_connect"))
    )
    (net (code "70") (name "unconnected-(IC1-~{TXLED}-Pad23)") (class "Default")
      (node (ref "IC1") (pin "23") (pinfunction "~{TXLED}_23") (pintype "input+no_connect"))
    )
    (net (code "71") (name "unconnected-(IC3-DP-Pad4)") (class "Default")
      (node (ref "IC3") (pin "4") (pinfunction "DP_4") (pintype "passive+no_connect"))
    )
    (net (code "72") (name "unconnected-(J1-CD{slash}DAT3^2-Pad2)") (class "Default")
      (node (ref "J1") (pin "2") (pinfunction "CD/DAT3^2_2") (pintype "passive+no_connect"))
    )
    (net (code "73") (name "unconnected-(J1-DAT2-Pad1)") (class "Default")
      (node (ref "J1") (pin "1") (pinfunction "DAT2_1") (pintype "passive+no_connect"))
    )
    (net (code "74") (name "unconnected-(J1-DETECT_SWITCH-Pad10)") (class "Default")
      (node (ref "J1") (pin "10") (pinfunction "DETECT_SWITCH_10") (pintype "passive+no_connect"))
    )
  )
)
